# Baro_V3.net
KiCad netlist of a schematic drawn in EAGLE
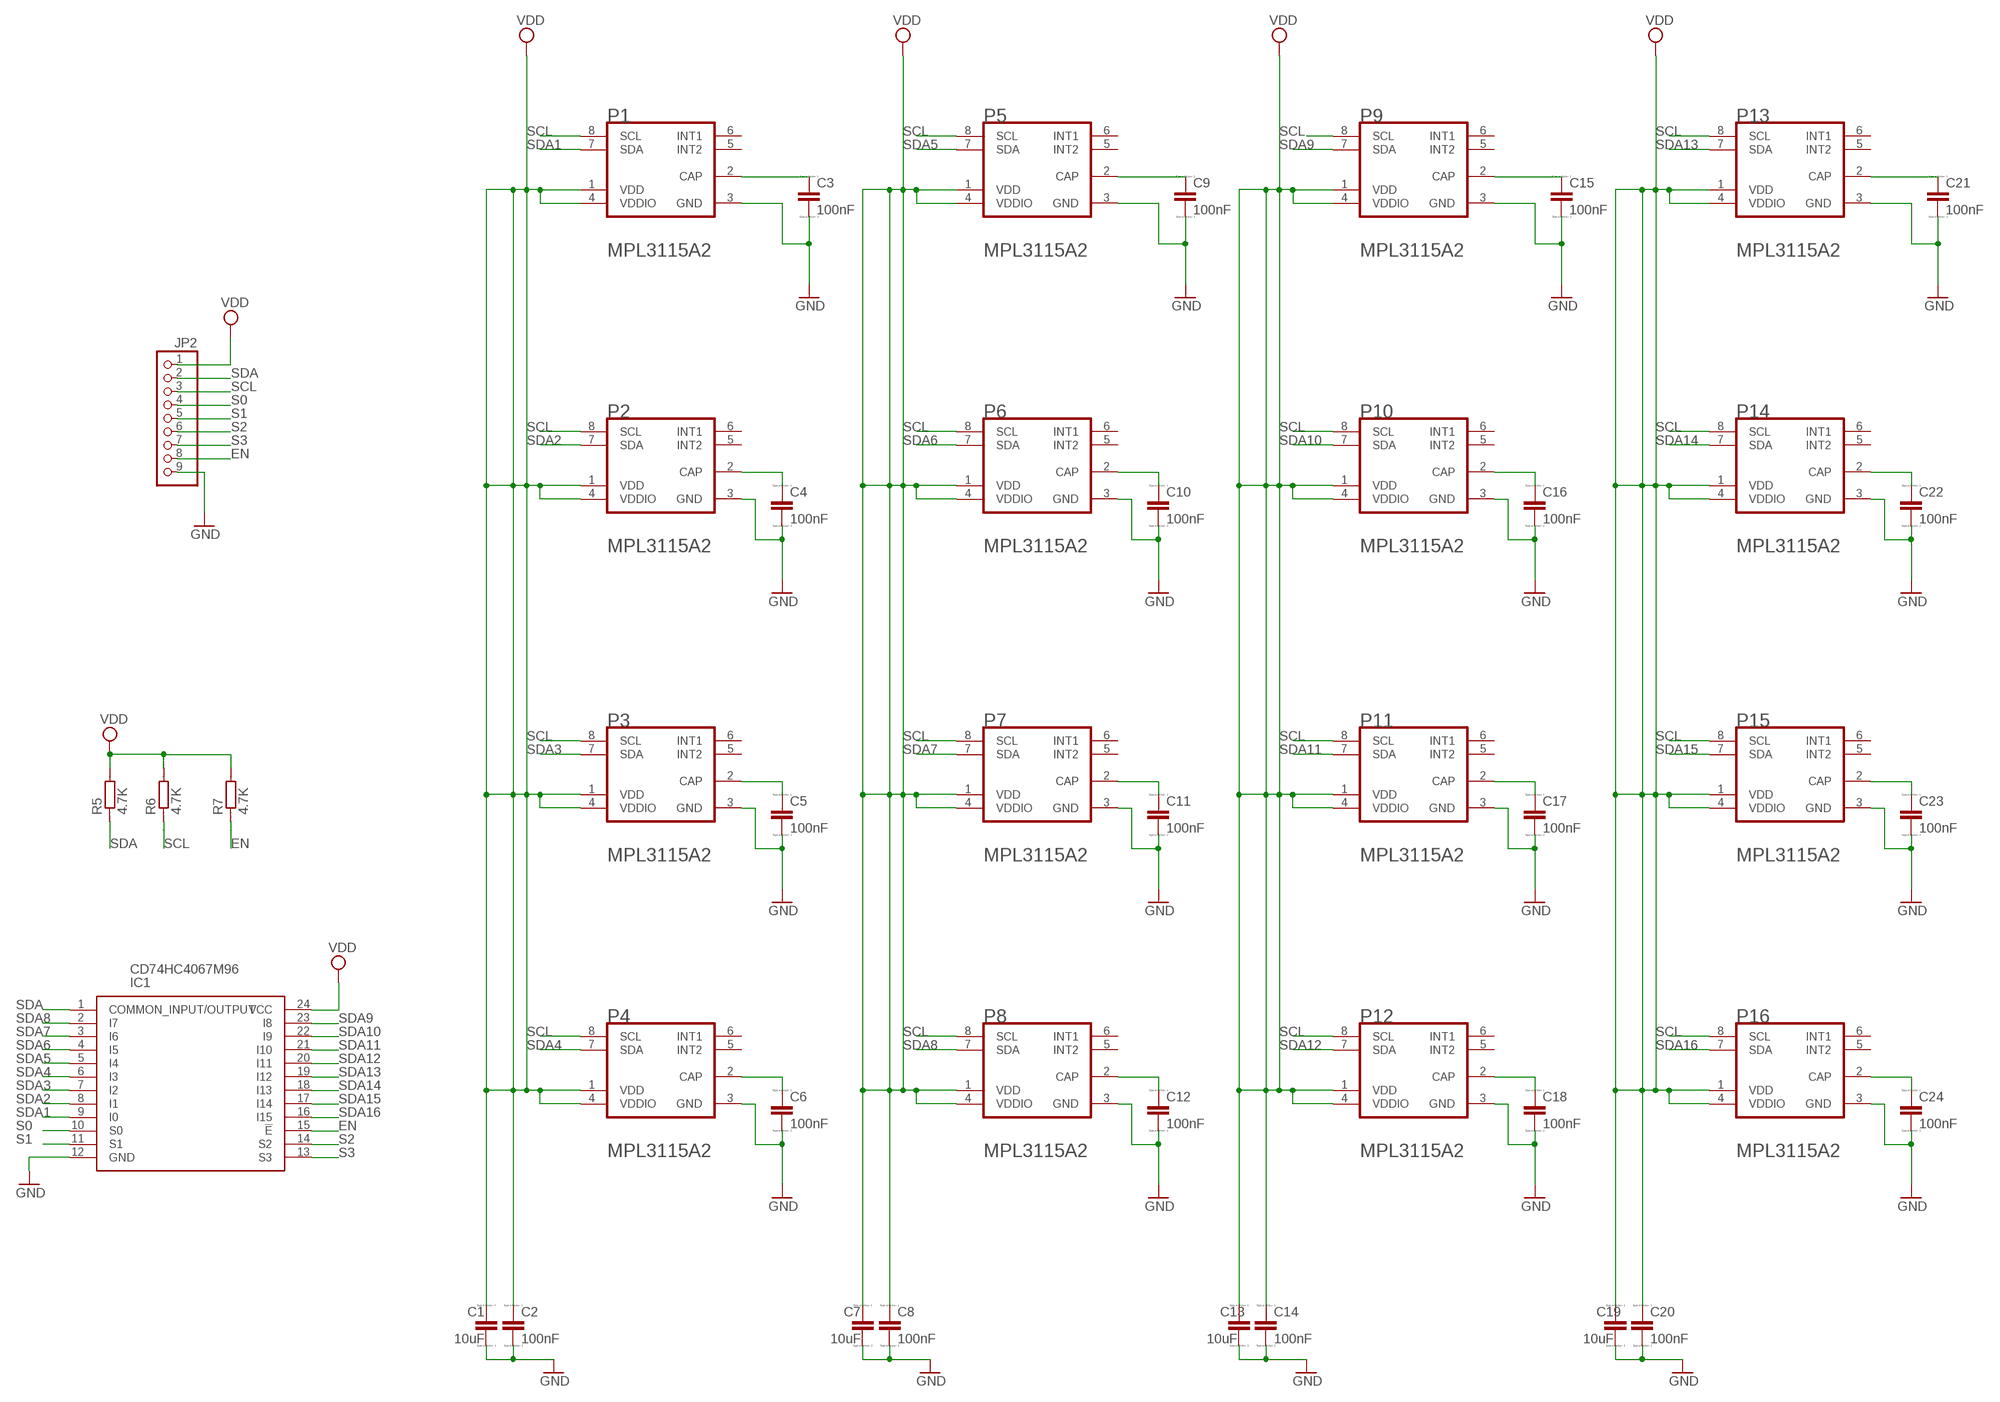
[diagram p0: schematic, sheet 1]

(export (version "E")
  (design (tool "Eeschema 10.0.6"))
  (components
    (comp (ref "C1")
      (value "10uF")
      (footprint "eagle-import:C0603")
      (libsource (lib "eagle-import") (part "CC0603"))
    )
    (comp (ref "C2")
      (value "100nF")
      (footprint "eagle-import:C0805")
      (libsource (lib "eagle-import") (part "C"))
    )
    (comp (ref "C3")
      (value "100nF")
      (footprint "eagle-import:C0805")
      (libsource (lib "eagle-import") (part "C"))
    )
    (comp (ref "C4")
      (value "100nF")
      (footprint "eagle-import:C0805")
      (libsource (lib "eagle-import") (part "C"))
    )
    (comp (ref "C5")
      (value "100nF")
      (footprint "eagle-import:C0805")
      (libsource (lib "eagle-import") (part "C"))
    )
    (comp (ref "C6")
      (value "100nF")
      (footprint "eagle-import:C0805")
      (libsource (lib "eagle-import") (part "C"))
    )
    (comp (ref "C7")
      (value "10uF")
      (footprint "eagle-import:C0603")
      (libsource (lib "eagle-import") (part "CC0603"))
    )
    (comp (ref "C8")
      (value "100nF")
      (footprint "eagle-import:C0805")
      (libsource (lib "eagle-import") (part "C"))
    )
    (comp (ref "C9")
      (value "100nF")
      (footprint "eagle-import:C0805")
      (libsource (lib "eagle-import") (part "C"))
    )
    (comp (ref "C10")
      (value "100nF")
      (footprint "eagle-import:C0805")
      (libsource (lib "eagle-import") (part "C"))
    )
    (comp (ref "C11")
      (value "100nF")
      (footprint "eagle-import:C0805")
      (libsource (lib "eagle-import") (part "C"))
    )
    (comp (ref "C12")
      (value "100nF")
      (footprint "eagle-import:C0805")
      (libsource (lib "eagle-import") (part "C"))
    )
    (comp (ref "C13")
      (value "10uF")
      (footprint "eagle-import:C0603")
      (libsource (lib "eagle-import") (part "CC0603"))
    )
    (comp (ref "C14")
      (value "100nF")
      (footprint "eagle-import:C0805")
      (libsource (lib "eagle-import") (part "C"))
    )
    (comp (ref "C15")
      (value "100nF")
      (footprint "eagle-import:C0805")
      (libsource (lib "eagle-import") (part "C"))
    )
    (comp (ref "C16")
      (value "100nF")
      (footprint "eagle-import:C0805")
      (libsource (lib "eagle-import") (part "C"))
    )
    (comp (ref "C17")
      (value "100nF")
      (footprint "eagle-import:C0805")
      (libsource (lib "eagle-import") (part "C"))
    )
    (comp (ref "C18")
      (value "100nF")
      (footprint "eagle-import:C0805")
      (libsource (lib "eagle-import") (part "C"))
    )
    (comp (ref "C19")
      (value "10uF")
      (footprint "eagle-import:C0603")
      (libsource (lib "eagle-import") (part "CC0603"))
    )
    (comp (ref "C20")
      (value "100nF")
      (footprint "eagle-import:C0805")
      (libsource (lib "eagle-import") (part "C"))
    )
    (comp (ref "C21")
      (value "100nF")
      (footprint "eagle-import:C0805")
      (libsource (lib "eagle-import") (part "C"))
    )
    (comp (ref "C22")
      (value "100nF")
      (footprint "eagle-import:C0805")
      (libsource (lib "eagle-import") (part "C"))
    )
    (comp (ref "C23")
      (value "100nF")
      (footprint "eagle-import:C0805")
      (libsource (lib "eagle-import") (part "C"))
    )
    (comp (ref "C24")
      (value "100nF")
      (footprint "eagle-import:C0805")
      (libsource (lib "eagle-import") (part "C"))
    )
    (comp (ref "IC1")
      (value "CD74HC4067M96")
      (footprint "eagle-import:SOIC127P1030X265-24N")
      (fields (field (name "MOUSER_PART_NUMBER") "595-CD74HC4067M96"))
      (libsource (lib "eagle-import") (part "CD74HC4067M96"))
    )
    (comp (ref "JP2")
      (value "PINHD-1X9")
      (footprint "eagle-import:1X09")
      (libsource (lib "eagle-import") (part "PINHD-1X9"))
    )
    (comp (ref "P1")
      (value "FREESCALE_SEMICONDUCTOR_MPL3115A2FREESCALE_SEMICONDUCTOR_MPL3115A2_0_0")
      (footprint "eagle-import:FREESCALE_SEMICONDUCTOR_MPL3115A2_0")
      (fields (field (name "MF") "Freescale Semiconductor") (field (name "MPN") "MPL3115A2"))
      (libsource (lib "eagle-import") (part "FREESCALE_SEMICONDUCTOR_MPL3115A2FREESCALE_SEMICONDUCTOR_MPL3115A2_0_0"))
    )
    (comp (ref "P2")
      (value "FREESCALE_SEMICONDUCTOR_MPL3115A2FREESCALE_SEMICONDUCTOR_MPL3115A2_0_0")
      (footprint "eagle-import:FREESCALE_SEMICONDUCTOR_MPL3115A2_0")
      (fields (field (name "MF") "Freescale Semiconductor") (field (name "MPN") "MPL3115A2"))
      (libsource (lib "eagle-import") (part "FREESCALE_SEMICONDUCTOR_MPL3115A2FREESCALE_SEMICONDUCTOR_MPL3115A2_0_0"))
    )
    (comp (ref "P3")
      (value "FREESCALE_SEMICONDUCTOR_MPL3115A2FREESCALE_SEMICONDUCTOR_MPL3115A2_0_0")
      (footprint "eagle-import:FREESCALE_SEMICONDUCTOR_MPL3115A2_0")
      (fields (field (name "MF") "Freescale Semiconductor") (field (name "MPN") "MPL3115A2"))
      (libsource (lib "eagle-import") (part "FREESCALE_SEMICONDUCTOR_MPL3115A2FREESCALE_SEMICONDUCTOR_MPL3115A2_0_0"))
    )
    (comp (ref "P4")
      (value "FREESCALE_SEMICONDUCTOR_MPL3115A2FREESCALE_SEMICONDUCTOR_MPL3115A2_0_0")
      (footprint "eagle-import:FREESCALE_SEMICONDUCTOR_MPL3115A2_0")
      (fields (field (name "MF") "Freescale Semiconductor") (field (name "MPN") "MPL3115A2"))
      (libsource (lib "eagle-import") (part "FREESCALE_SEMICONDUCTOR_MPL3115A2FREESCALE_SEMICONDUCTOR_MPL3115A2_0_0"))
    )
    (comp (ref "P5")
      (value "FREESCALE_SEMICONDUCTOR_MPL3115A2FREESCALE_SEMICONDUCTOR_MPL3115A2_0_0")
      (footprint "eagle-import:FREESCALE_SEMICONDUCTOR_MPL3115A2_0")
      (fields (field (name "MF") "Freescale Semiconductor") (field (name "MPN") "MPL3115A2"))
      (libsource (lib "eagle-import") (part "FREESCALE_SEMICONDUCTOR_MPL3115A2FREESCALE_SEMICONDUCTOR_MPL3115A2_0_0"))
    )
    (comp (ref "P6")
      (value "FREESCALE_SEMICONDUCTOR_MPL3115A2FREESCALE_SEMICONDUCTOR_MPL3115A2_0_0")
      (footprint "eagle-import:FREESCALE_SEMICONDUCTOR_MPL3115A2_0")
      (fields (field (name "MF") "Freescale Semiconductor") (field (name "MPN") "MPL3115A2"))
      (libsource (lib "eagle-import") (part "FREESCALE_SEMICONDUCTOR_MPL3115A2FREESCALE_SEMICONDUCTOR_MPL3115A2_0_0"))
    )
    (comp (ref "P7")
      (value "FREESCALE_SEMICONDUCTOR_MPL3115A2FREESCALE_SEMICONDUCTOR_MPL3115A2_0_0")
      (footprint "eagle-import:FREESCALE_SEMICONDUCTOR_MPL3115A2_0")
      (fields (field (name "MF") "Freescale Semiconductor") (field (name "MPN") "MPL3115A2"))
      (libsource (lib "eagle-import") (part "FREESCALE_SEMICONDUCTOR_MPL3115A2FREESCALE_SEMICONDUCTOR_MPL3115A2_0_0"))
    )
    (comp (ref "P8")
      (value "FREESCALE_SEMICONDUCTOR_MPL3115A2FREESCALE_SEMICONDUCTOR_MPL3115A2_0_0")
      (footprint "eagle-import:FREESCALE_SEMICONDUCTOR_MPL3115A2_0")
      (fields (field (name "MF") "Freescale Semiconductor") (field (name "MPN") "MPL3115A2"))
      (libsource (lib "eagle-import") (part "FREESCALE_SEMICONDUCTOR_MPL3115A2FREESCALE_SEMICONDUCTOR_MPL3115A2_0_0"))
    )
    (comp (ref "P9")
      (value "FREESCALE_SEMICONDUCTOR_MPL3115A2FREESCALE_SEMICONDUCTOR_MPL3115A2_0_0")
      (footprint "eagle-import:FREESCALE_SEMICONDUCTOR_MPL3115A2_0")
      (fields (field (name "MF") "Freescale Semiconductor") (field (name "MPN") "MPL3115A2"))
      (libsource (lib "eagle-import") (part "FREESCALE_SEMICONDUCTOR_MPL3115A2FREESCALE_SEMICONDUCTOR_MPL3115A2_0_0"))
    )
    (comp (ref "P10")
      (value "FREESCALE_SEMICONDUCTOR_MPL3115A2FREESCALE_SEMICONDUCTOR_MPL3115A2_0_0")
      (footprint "eagle-import:FREESCALE_SEMICONDUCTOR_MPL3115A2_0")
      (fields (field (name "MF") "Freescale Semiconductor") (field (name "MPN") "MPL3115A2"))
      (libsource (lib "eagle-import") (part "FREESCALE_SEMICONDUCTOR_MPL3115A2FREESCALE_SEMICONDUCTOR_MPL3115A2_0_0"))
    )
    (comp (ref "P11")
      (value "FREESCALE_SEMICONDUCTOR_MPL3115A2FREESCALE_SEMICONDUCTOR_MPL3115A2_0_0")
      (footprint "eagle-import:FREESCALE_SEMICONDUCTOR_MPL3115A2_0")
      (fields (field (name "MF") "Freescale Semiconductor") (field (name "MPN") "MPL3115A2"))
      (libsource (lib "eagle-import") (part "FREESCALE_SEMICONDUCTOR_MPL3115A2FREESCALE_SEMICONDUCTOR_MPL3115A2_0_0"))
    )
    (comp (ref "P12")
      (value "FREESCALE_SEMICONDUCTOR_MPL3115A2FREESCALE_SEMICONDUCTOR_MPL3115A2_0_0")
      (footprint "eagle-import:FREESCALE_SEMICONDUCTOR_MPL3115A2_0")
      (fields (field (name "MF") "Freescale Semiconductor") (field (name "MPN") "MPL3115A2"))
      (libsource (lib "eagle-import") (part "FREESCALE_SEMICONDUCTOR_MPL3115A2FREESCALE_SEMICONDUCTOR_MPL3115A2_0_0"))
    )
    (comp (ref "P13")
      (value "FREESCALE_SEMICONDUCTOR_MPL3115A2FREESCALE_SEMICONDUCTOR_MPL3115A2_0_0")
      (footprint "eagle-import:FREESCALE_SEMICONDUCTOR_MPL3115A2_0")
      (fields (field (name "MF") "Freescale Semiconductor") (field (name "MPN") "MPL3115A2"))
      (libsource (lib "eagle-import") (part "FREESCALE_SEMICONDUCTOR_MPL3115A2FREESCALE_SEMICONDUCTOR_MPL3115A2_0_0"))
    )
    (comp (ref "P14")
      (value "FREESCALE_SEMICONDUCTOR_MPL3115A2FREESCALE_SEMICONDUCTOR_MPL3115A2_0_0")
      (footprint "eagle-import:FREESCALE_SEMICONDUCTOR_MPL3115A2_0")
      (fields (field (name "MF") "Freescale Semiconductor") (field (name "MPN") "MPL3115A2"))
      (libsource (lib "eagle-import") (part "FREESCALE_SEMICONDUCTOR_MPL3115A2FREESCALE_SEMICONDUCTOR_MPL3115A2_0_0"))
    )
    (comp (ref "P15")
      (value "FREESCALE_SEMICONDUCTOR_MPL3115A2FREESCALE_SEMICONDUCTOR_MPL3115A2_0_0")
      (footprint "eagle-import:FREESCALE_SEMICONDUCTOR_MPL3115A2_0")
      (fields (field (name "MF") "Freescale Semiconductor") (field (name "MPN") "MPL3115A2"))
      (libsource (lib "eagle-import") (part "FREESCALE_SEMICONDUCTOR_MPL3115A2FREESCALE_SEMICONDUCTOR_MPL3115A2_0_0"))
    )
    (comp (ref "P16")
      (value "FREESCALE_SEMICONDUCTOR_MPL3115A2FREESCALE_SEMICONDUCTOR_MPL3115A2_0_0")
      (footprint "eagle-import:FREESCALE_SEMICONDUCTOR_MPL3115A2_0")
      (fields (field (name "MF") "Freescale Semiconductor") (field (name "MPN") "MPL3115A2"))
      (libsource (lib "eagle-import") (part "FREESCALE_SEMICONDUCTOR_MPL3115A2FREESCALE_SEMICONDUCTOR_MPL3115A2_0_0"))
    )
    (comp (ref "R5")
      (value "4.7K")
      (footprint "eagle-import:R0603")
      (libsource (lib "eagle-import") (part "RR0603"))
    )
    (comp (ref "R6")
      (value "4.7K")
      (footprint "eagle-import:R0603")
      (libsource (lib "eagle-import") (part "RR0603"))
    )
    (comp (ref "R7")
      (value "4.7K")
      (footprint "eagle-import:R0603")
      (libsource (lib "eagle-import") (part "RR0603"))
    )
  )
  (nets
    (net (code "1") (name "/EN") (class "Default")
      (node (ref "IC1") (pin "15") (pinfunction "~{E}_15") (pintype "bidirectional"))
      (node (ref "JP2") (pin "8") (pinfunction "8_8") (pintype "passive"))
      (node (ref "R7") (pin "1") (pinfunction "1_1") (pintype "passive"))
    )
    (net (code "2") (name "/S0") (class "Default")
      (node (ref "IC1") (pin "10") (pinfunction "S0_10") (pintype "bidirectional"))
      (node (ref "JP2") (pin "4") (pinfunction "4_4") (pintype "passive"))
    )
    (net (code "3") (name "/S1") (class "Default")
      (node (ref "IC1") (pin "11") (pinfunction "S1_11") (pintype "bidirectional"))
      (node (ref "JP2") (pin "5") (pinfunction "5_5") (pintype "passive"))
    )
    (net (code "4") (name "/S2") (class "Default")
      (node (ref "IC1") (pin "14") (pinfunction "S2_14") (pintype "bidirectional"))
      (node (ref "JP2") (pin "6") (pinfunction "6_6") (pintype "passive"))
    )
    (net (code "5") (name "/S3") (class "Default")
      (node (ref "IC1") (pin "13") (pinfunction "S3_13") (pintype "bidirectional"))
      (node (ref "JP2") (pin "7") (pinfunction "7_7") (pintype "passive"))
    )
    (net (code "6") (name "/SCL") (class "Default")
      (node (ref "JP2") (pin "3") (pinfunction "3_3") (pintype "passive"))
      (node (ref "P1") (pin "8") (pinfunction "SCL_8") (pintype "input"))
      (node (ref "P10") (pin "8") (pinfunction "SCL_8") (pintype "input"))
      (node (ref "P11") (pin "8") (pinfunction "SCL_8") (pintype "input"))
      (node (ref "P12") (pin "8") (pinfunction "SCL_8") (pintype "input"))
      (node (ref "P13") (pin "8") (pinfunction "SCL_8") (pintype "input"))
      (node (ref "P14") (pin "8") (pinfunction "SCL_8") (pintype "input"))
      (node (ref "P15") (pin "8") (pinfunction "SCL_8") (pintype "input"))
      (node (ref "P16") (pin "8") (pinfunction "SCL_8") (pintype "input"))
      (node (ref "P2") (pin "8") (pinfunction "SCL_8") (pintype "input"))
      (node (ref "P3") (pin "8") (pinfunction "SCL_8") (pintype "input"))
      (node (ref "P4") (pin "8") (pinfunction "SCL_8") (pintype "input"))
      (node (ref "P5") (pin "8") (pinfunction "SCL_8") (pintype "input"))
      (node (ref "P6") (pin "8") (pinfunction "SCL_8") (pintype "input"))
      (node (ref "P7") (pin "8") (pinfunction "SCL_8") (pintype "input"))
      (node (ref "P8") (pin "8") (pinfunction "SCL_8") (pintype "input"))
      (node (ref "P9") (pin "8") (pinfunction "SCL_8") (pintype "input"))
      (node (ref "R6") (pin "1") (pinfunction "1_1") (pintype "passive"))
    )
    (net (code "7") (name "/SDA") (class "Default")
      (node (ref "IC1") (pin "1") (pinfunction "COMMON_INPUT/OUTPUT_1") (pintype "bidirectional"))
      (node (ref "JP2") (pin "2") (pinfunction "2_2") (pintype "passive"))
      (node (ref "R5") (pin "1") (pinfunction "1_1") (pintype "passive"))
    )
    (net (code "8") (name "/SDA1") (class "Default")
      (node (ref "IC1") (pin "9") (pinfunction "I0_9") (pintype "bidirectional"))
      (node (ref "P1") (pin "7") (pinfunction "SDA_7") (pintype "bidirectional"))
    )
    (net (code "9") (name "/SDA2") (class "Default")
      (node (ref "IC1") (pin "8") (pinfunction "I1_8") (pintype "bidirectional"))
      (node (ref "P2") (pin "7") (pinfunction "SDA_7") (pintype "bidirectional"))
    )
    (net (code "10") (name "/SDA3") (class "Default")
      (node (ref "IC1") (pin "7") (pinfunction "I2_7") (pintype "bidirectional"))
      (node (ref "P3") (pin "7") (pinfunction "SDA_7") (pintype "bidirectional"))
    )
    (net (code "11") (name "/SDA4") (class "Default")
      (node (ref "IC1") (pin "6") (pinfunction "I3_6") (pintype "bidirectional"))
      (node (ref "P4") (pin "7") (pinfunction "SDA_7") (pintype "bidirectional"))
    )
    (net (code "12") (name "/SDA5") (class "Default")
      (node (ref "IC1") (pin "5") (pinfunction "I4_5") (pintype "bidirectional"))
      (node (ref "P5") (pin "7") (pinfunction "SDA_7") (pintype "bidirectional"))
    )
    (net (code "13") (name "/SDA6") (class "Default")
      (node (ref "IC1") (pin "4") (pinfunction "I5_4") (pintype "bidirectional"))
      (node (ref "P6") (pin "7") (pinfunction "SDA_7") (pintype "bidirectional"))
    )
    (net (code "14") (name "/SDA7") (class "Default")
      (node (ref "IC1") (pin "3") (pinfunction "I6_3") (pintype "bidirectional"))
      (node (ref "P7") (pin "7") (pinfunction "SDA_7") (pintype "bidirectional"))
    )
    (net (code "15") (name "/SDA8") (class "Default")
      (node (ref "IC1") (pin "2") (pinfunction "I7_2") (pintype "bidirectional"))
      (node (ref "P8") (pin "7") (pinfunction "SDA_7") (pintype "bidirectional"))
    )
    (net (code "16") (name "/SDA9") (class "Default")
      (node (ref "IC1") (pin "23") (pinfunction "I8_23") (pintype "bidirectional"))
      (node (ref "P9") (pin "7") (pinfunction "SDA_7") (pintype "bidirectional"))
    )
    (net (code "17") (name "/SDA10") (class "Default")
      (node (ref "IC1") (pin "22") (pinfunction "I9_22") (pintype "bidirectional"))
      (node (ref "P10") (pin "7") (pinfunction "SDA_7") (pintype "bidirectional"))
    )
    (net (code "18") (name "/SDA11") (class "Default")
      (node (ref "IC1") (pin "21") (pinfunction "I10_21") (pintype "bidirectional"))
      (node (ref "P11") (pin "7") (pinfunction "SDA_7") (pintype "bidirectional"))
    )
    (net (code "19") (name "/SDA12") (class "Default")
      (node (ref "IC1") (pin "20") (pinfunction "I11_20") (pintype "bidirectional"))
      (node (ref "P12") (pin "7") (pinfunction "SDA_7") (pintype "bidirectional"))
    )
    (net (code "20") (name "/SDA13") (class "Default")
      (node (ref "IC1") (pin "19") (pinfunction "I12_19") (pintype "bidirectional"))
      (node (ref "P13") (pin "7") (pinfunction "SDA_7") (pintype "bidirectional"))
    )
    (net (code "21") (name "/SDA14") (class "Default")
      (node (ref "IC1") (pin "18") (pinfunction "I13_18") (pintype "bidirectional"))
      (node (ref "P14") (pin "7") (pinfunction "SDA_7") (pintype "bidirectional"))
    )
    (net (code "22") (name "/SDA15") (class "Default")
      (node (ref "IC1") (pin "17") (pinfunction "I14_17") (pintype "bidirectional"))
      (node (ref "P15") (pin "7") (pinfunction "SDA_7") (pintype "bidirectional"))
    )
    (net (code "23") (name "/SDA16") (class "Default")
      (node (ref "IC1") (pin "16") (pinfunction "I15_16") (pintype "bidirectional"))
      (node (ref "P16") (pin "7") (pinfunction "SDA_7") (pintype "bidirectional"))
    )
    (net (code "24") (name "GND") (class "Default")
      (node (ref "C1") (pin "2") (pinfunction "2_2") (pintype "passive"))
      (node (ref "C10") (pin "2") (pinfunction "2_2") (pintype "passive"))
      (node (ref "C11") (pin "2") (pinfunction "2_2") (pintype "passive"))
      (node (ref "C12") (pin "2") (pinfunction "2_2") (pintype "passive"))
      (node (ref "C13") (pin "2") (pinfunction "2_2") (pintype "passive"))
      (node (ref "C14") (pin "2") (pinfunction "2_2") (pintype "passive"))
      (node (ref "C15") (pin "2") (pinfunction "2_2") (pintype "passive"))
      (node (ref "C16") (pin "2") (pinfunction "2_2") (pintype "passive"))
      (node (ref "C17") (pin "2") (pinfunction "2_2") (pintype "passive"))
      (node (ref "C18") (pin "2") (pinfunction "2_2") (pintype "passive"))
      (node (ref "C19") (pin "2") (pinfunction "2_2") (pintype "passive"))
      (node (ref "C2") (pin "2") (pinfunction "2_2") (pintype "passive"))
      (node (ref "C20") (pin "2") (pinfunction "2_2") (pintype "passive"))
      (node (ref "C21") (pin "2") (pinfunction "2_2") (pintype "passive"))
      (node (ref "C22") (pin "2") (pinfunction "2_2") (pintype "passive"))
      (node (ref "C23") (pin "2") (pinfunction "2_2") (pintype "passive"))
      (node (ref "C24") (pin "2") (pinfunction "2_2") (pintype "passive"))
      (node (ref "C3") (pin "2") (pinfunction "2_2") (pintype "passive"))
      (node (ref "C4") (pin "2") (pinfunction "2_2") (pintype "passive"))
      (node (ref "C5") (pin "2") (pinfunction "2_2") (pintype "passive"))
      (node (ref "C6") (pin "2") (pinfunction "2_2") (pintype "passive"))
      (node (ref "C7") (pin "2") (pinfunction "2_2") (pintype "passive"))
      (node (ref "C8") (pin "2") (pinfunction "2_2") (pintype "passive"))
      (node (ref "C9") (pin "2") (pinfunction "2_2") (pintype "passive"))
      (node (ref "IC1") (pin "12") (pinfunction "GND_12") (pintype "bidirectional"))
      (node (ref "JP2") (pin "9") (pinfunction "9_9") (pintype "passive"))
      (node (ref "P1") (pin "3") (pinfunction "GND_3") (pintype "power_in"))
      (node (ref "P10") (pin "3") (pinfunction "GND_3") (pintype "power_in"))
      (node (ref "P11") (pin "3") (pinfunction "GND_3") (pintype "power_in"))
      (node (ref "P12") (pin "3") (pinfunction "GND_3") (pintype "power_in"))
      (node (ref "P13") (pin "3") (pinfunction "GND_3") (pintype "power_in"))
      (node (ref "P14") (pin "3") (pinfunction "GND_3") (pintype "power_in"))
      (node (ref "P15") (pin "3") (pinfunction "GND_3") (pintype "power_in"))
      (node (ref "P16") (pin "3") (pinfunction "GND_3") (pintype "power_in"))
      (node (ref "P2") (pin "3") (pinfunction "GND_3") (pintype "power_in"))
      (node (ref "P3") (pin "3") (pinfunction "GND_3") (pintype "power_in"))
      (node (ref "P4") (pin "3") (pinfunction "GND_3") (pintype "power_in"))
      (node (ref "P5") (pin "3") (pinfunction "GND_3") (pintype "power_in"))
      (node (ref "P6") (pin "3") (pinfunction "GND_3") (pintype "power_in"))
      (node (ref "P7") (pin "3") (pinfunction "GND_3") (pintype "power_in"))
      (node (ref "P8") (pin "3") (pinfunction "GND_3") (pintype "power_in"))
      (node (ref "P9") (pin "3") (pinfunction "GND_3") (pintype "power_in"))
    )
    (net (code "25") (name "Net-(P1-CAP)") (class "Default")
      (node (ref "C3") (pin "1") (pinfunction "1_1") (pintype "passive"))
      (node (ref "P1") (pin "2") (pinfunction "CAP_2") (pintype "passive"))
    )
    (net (code "26") (name "Net-(P2-CAP)") (class "Default")
      (node (ref "C4") (pin "1") (pinfunction "1_1") (pintype "passive"))
      (node (ref "P2") (pin "2") (pinfunction "CAP_2") (pintype "passive"))
    )
    (net (code "27") (name "Net-(P3-CAP)") (class "Default")
      (node (ref "C5") (pin "1") (pinfunction "1_1") (pintype "passive"))
      (node (ref "P3") (pin "2") (pinfunction "CAP_2") (pintype "passive"))
    )
    (net (code "28") (name "Net-(P4-CAP)") (class "Default")
      (node (ref "C6") (pin "1") (pinfunction "1_1") (pintype "passive"))
      (node (ref "P4") (pin "2") (pinfunction "CAP_2") (pintype "passive"))
    )
    (net (code "29") (name "Net-(P5-CAP)") (class "Default")
      (node (ref "C9") (pin "1") (pinfunction "1_1") (pintype "passive"))
      (node (ref "P5") (pin "2") (pinfunction "CAP_2") (pintype "passive"))
    )
    (net (code "30") (name "Net-(P6-CAP)") (class "Default")
      (node (ref "C10") (pin "1") (pinfunction "1_1") (pintype "passive"))
      (node (ref "P6") (pin "2") (pinfunction "CAP_2") (pintype "passive"))
    )
    (net (code "31") (name "Net-(P7-CAP)") (class "Default")
      (node (ref "C11") (pin "1") (pinfunction "1_1") (pintype "passive"))
      (node (ref "P7") (pin "2") (pinfunction "CAP_2") (pintype "passive"))
    )
    (net (code "32") (name "Net-(P8-CAP)") (class "Default")
      (node (ref "C12") (pin "1") (pinfunction "1_1") (pintype "passive"))
      (node (ref "P8") (pin "2") (pinfunction "CAP_2") (pintype "passive"))
    )
    (net (code "33") (name "Net-(P9-CAP)") (class "Default")
      (node (ref "C15") (pin "1") (pinfunction "1_1") (pintype "passive"))
      (node (ref "P9") (pin "2") (pinfunction "CAP_2") (pintype "passive"))
    )
    (net (code "34") (name "Net-(P10-CAP)") (class "Default")
      (node (ref "C16") (pin "1") (pinfunction "1_1") (pintype "passive"))
      (node (ref "P10") (pin "2") (pinfunction "CAP_2") (pintype "passive"))
    )
    (net (code "35") (name "Net-(P11-CAP)") (class "Default")
      (node (ref "C17") (pin "1") (pinfunction "1_1") (pintype "passive"))
      (node (ref "P11") (pin "2") (pinfunction "CAP_2") (pintype "passive"))
    )
    (net (code "36") (name "Net-(P12-CAP)") (class "Default")
      (node (ref "C18") (pin "1") (pinfunction "1_1") (pintype "passive"))
      (node (ref "P12") (pin "2") (pinfunction "CAP_2") (pintype "passive"))
    )
    (net (code "37") (name "Net-(P13-CAP)") (class "Default")
      (node (ref "C21") (pin "1") (pinfunction "1_1") (pintype "passive"))
      (node (ref "P13") (pin "2") (pinfunction "CAP_2") (pintype "passive"))
    )
    (net (code "38") (name "Net-(P14-CAP)") (class "Default")
      (node (ref "C22") (pin "1") (pinfunction "1_1") (pintype "passive"))
      (node (ref "P14") (pin "2") (pinfunction "CAP_2") (pintype "passive"))
    )
    (net (code "39") (name "Net-(P15-CAP)") (class "Default")
      (node (ref "C23") (pin "1") (pinfunction "1_1") (pintype "passive"))
      (node (ref "P15") (pin "2") (pinfunction "CAP_2") (pintype "passive"))
    )
    (net (code "40") (name "Net-(P16-CAP)") (class "Default")
      (node (ref "C24") (pin "1") (pinfunction "1_1") (pintype "passive"))
      (node (ref "P16") (pin "2") (pinfunction "CAP_2") (pintype "passive"))
    )
    (net (code "41") (name "VDD") (class "Default")
      (node (ref "C1") (pin "1") (pinfunction "1_1") (pintype "passive"))
      (node (ref "C13") (pin "1") (pinfunction "1_1") (pintype "passive"))
      (node (ref "C14") (pin "1") (pinfunction "1_1") (pintype "passive"))
      (node (ref "C19") (pin "1") (pinfunction "1_1") (pintype "passive"))
      (node (ref "C2") (pin "1") (pinfunction "1_1") (pintype "passive"))
      (node (ref "C20") (pin "1") (pinfunction "1_1") (pintype "passive"))
      (node (ref "C7") (pin "1") (pinfunction "1_1") (pintype "passive"))
      (node (ref "C8") (pin "1") (pinfunction "1_1") (pintype "passive"))
      (node (ref "IC1") (pin "24") (pinfunction "VCC_24") (pintype "bidirectional"))
      (node (ref "JP2") (pin "1") (pinfunction "1_1") (pintype "passive"))
      (node (ref "P1") (pin "1") (pinfunction "VDD_1") (pintype "power_in"))
      (node (ref "P1") (pin "4") (pinfunction "VDDIO_4") (pintype "power_in"))
      (node (ref "P10") (pin "1") (pinfunction "VDD_1") (pintype "power_in"))
      (node (ref "P10") (pin "4") (pinfunction "VDDIO_4") (pintype "power_in"))
      (node (ref "P11") (pin "1") (pinfunction "VDD_1") (pintype "power_in"))
      (node (ref "P11") (pin "4") (pinfunction "VDDIO_4") (pintype "power_in"))
      (node (ref "P12") (pin "1") (pinfunction "VDD_1") (pintype "power_in"))
      (node (ref "P12") (pin "4") (pinfunction "VDDIO_4") (pintype "power_in"))
      (node (ref "P13") (pin "1") (pinfunction "VDD_1") (pintype "power_in"))
      (node (ref "P13") (pin "4") (pinfunction "VDDIO_4") (pintype "power_in"))
      (node (ref "P14") (pin "1") (pinfunction "VDD_1") (pintype "power_in"))
      (node (ref "P14") (pin "4") (pinfunction "VDDIO_4") (pintype "power_in"))
      (node (ref "P15") (pin "1") (pinfunction "VDD_1") (pintype "power_in"))
      (node (ref "P15") (pin "4") (pinfunction "VDDIO_4") (pintype "power_in"))
      (node (ref "P16") (pin "1") (pinfunction "VDD_1") (pintype "power_in"))
      (node (ref "P16") (pin "4") (pinfunction "VDDIO_4") (pintype "power_in"))
      (node (ref "P2") (pin "1") (pinfunction "VDD_1") (pintype "power_in"))
      (node (ref "P2") (pin "4") (pinfunction "VDDIO_4") (pintype "power_in"))
      (node (ref "P3") (pin "1") (pinfunction "VDD_1") (pintype "power_in"))
      (node (ref "P3") (pin "4") (pinfunction "VDDIO_4") (pintype "power_in"))
      (node (ref "P4") (pin "1") (pinfunction "VDD_1") (pintype "power_in"))
      (node (ref "P4") (pin "4") (pinfunction "VDDIO_4") (pintype "power_in"))
      (node (ref "P5") (pin "1") (pinfunction "VDD_1") (pintype "power_in"))
      (node (ref "P5") (pin "4") (pinfunction "VDDIO_4") (pintype "power_in"))
      (node (ref "P6") (pin "1") (pinfunction "VDD_1") (pintype "power_in"))
      (node (ref "P6") (pin "4") (pinfunction "VDDIO_4") (pintype "power_in"))
      (node (ref "P7") (pin "1") (pinfunction "VDD_1") (pintype "power_in"))
      (node (ref "P7") (pin "4") (pinfunction "VDDIO_4") (pintype "power_in"))
      (node (ref "P8") (pin "1") (pinfunction "VDD_1") (pintype "power_in"))
      (node (ref "P8") (pin "4") (pinfunction "VDDIO_4") (pintype "power_in"))
      (node (ref "P9") (pin "1") (pinfunction "VDD_1") (pintype "power_in"))
      (node (ref "P9") (pin "4") (pinfunction "VDDIO_4") (pintype "power_in"))
      (node (ref "R5") (pin "2") (pinfunction "2_2") (pintype "passive"))
      (node (ref "R6") (pin "2") (pinfunction "2_2") (pintype "passive"))
      (node (ref "R7") (pin "2") (pinfunction "2_2") (pintype "passive"))
    )
    (net (code "42") (name "unconnected-(P1-INT1-Pad6)") (class "Default")
      (node (ref "P1") (pin "6") (pinfunction "INT1_6") (pintype "output"))
    )
    (net (code "43") (name "unconnected-(P1-INT2-Pad5)") (class "Default")
      (node (ref "P1") (pin "5") (pinfunction "INT2_5") (pintype "output"))
    )
    (net (code "44") (name "unconnected-(P2-INT1-Pad6)") (class "Default")
      (node (ref "P2") (pin "6") (pinfunction "INT1_6") (pintype "output"))
    )
    (net (code "45") (name "unconnected-(P2-INT2-Pad5)") (class "Default")
      (node (ref "P2") (pin "5") (pinfunction "INT2_5") (pintype "output"))
    )
    (net (code "46") (name "unconnected-(P3-INT1-Pad6)") (class "Default")
      (node (ref "P3") (pin "6") (pinfunction "INT1_6") (pintype "output"))
    )
    (net (code "47") (name "unconnected-(P3-INT2-Pad5)") (class "Default")
      (node (ref "P3") (pin "5") (pinfunction "INT2_5") (pintype "output"))
    )
    (net (code "48") (name "unconnected-(P4-INT1-Pad6)") (class "Default")
      (node (ref "P4") (pin "6") (pinfunction "INT1_6") (pintype "output"))
    )
    (net (code "49") (name "unconnected-(P4-INT2-Pad5)") (class "Default")
      (node (ref "P4") (pin "5") (pinfunction "INT2_5") (pintype "output"))
    )
    (net (code "50") (name "unconnected-(P5-INT1-Pad6)") (class "Default")
      (node (ref "P5") (pin "6") (pinfunction "INT1_6") (pintype "output"))
    )
    (net (code "51") (name "unconnected-(P5-INT2-Pad5)") (class "Default")
      (node (ref "P5") (pin "5") (pinfunction "INT2_5") (pintype "output"))
    )
    (net (code "52") (name "unconnected-(P6-INT1-Pad6)") (class "Default")
      (node (ref "P6") (pin "6") (pinfunction "INT1_6") (pintype "output"))
    )
    (net (code "53") (name "unconnected-(P6-INT2-Pad5)") (class "Default")
      (node (ref "P6") (pin "5") (pinfunction "INT2_5") (pintype "output"))
    )
    (net (code "54") (name "unconnected-(P7-INT1-Pad6)") (class "Default")
      (node (ref "P7") (pin "6") (pinfunction "INT1_6") (pintype "output"))
    )
    (net (code "55") (name "unconnected-(P7-INT2-Pad5)") (class "Default")
      (node (ref "P7") (pin "5") (pinfunction "INT2_5") (pintype "output"))
    )
    (net (code "56") (name "unconnected-(P8-INT1-Pad6)") (class "Default")
      (node (ref "P8") (pin "6") (pinfunction "INT1_6") (pintype "output"))
    )
    (net (code "57") (name "unconnected-(P8-INT2-Pad5)") (class "Default")
      (node (ref "P8") (pin "5") (pinfunction "INT2_5") (pintype "output"))
    )
    (net (code "58") (name "unconnected-(P9-INT1-Pad6)") (class "Default")
      (node (ref "P9") (pin "6") (pinfunction "INT1_6") (pintype "output"))
    )
    (net (code "59") (name "unconnected-(P9-INT2-Pad5)") (class "Default")
      (node (ref "P9") (pin "5") (pinfunction "INT2_5") (pintype "output"))
    )
    (net (code "60") (name "unconnected-(P10-INT1-Pad6)") (class "Default")
      (node (ref "P10") (pin "6") (pinfunction "INT1_6") (pintype "output"))
    )
    (net (code "61") (name "unconnected-(P10-INT2-Pad5)") (class "Default")
      (node (ref "P10") (pin "5") (pinfunction "INT2_5") (pintype "output"))
    )
    (net (code "62") (name "unconnected-(P11-INT1-Pad6)") (class "Default")
      (node (ref "P11") (pin "6") (pinfunction "INT1_6") (pintype "output"))
    )
    (net (code "63") (name "unconnected-(P11-INT2-Pad5)") (class "Default")
      (node (ref "P11") (pin "5") (pinfunction "INT2_5") (pintype "output"))
    )
    (net (code "64") (name "unconnected-(P12-INT1-Pad6)") (class "Default")
      (node (ref "P12") (pin "6") (pinfunction "INT1_6") (pintype "output"))
    )
    (net (code "65") (name "unconnected-(P12-INT2-Pad5)") (class "Default")
      (node (ref "P12") (pin "5") (pinfunction "INT2_5") (pintype "output"))
    )
    (net (code "66") (name "unconnected-(P13-INT1-Pad6)") (class "Default")
      (node (ref "P13") (pin "6") (pinfunction "INT1_6") (pintype "output"))
    )
    (net (code "67") (name "unconnected-(P13-INT2-Pad5)") (class "Default")
      (node (ref "P13") (pin "5") (pinfunction "INT2_5") (pintype "output"))
    )
    (net (code "68") (name "unconnected-(P14-INT1-Pad6)") (class "Default")
      (node (ref "P14") (pin "6") (pinfunction "INT1_6") (pintype "output"))
    )
    (net (code "69") (name "unconnected-(P14-INT2-Pad5)") (class "Default")
      (node (ref "P14") (pin "5") (pinfunction "INT2_5") (pintype "output"))
    )
    (net (code "70") (name "unconnected-(P15-INT1-Pad6)") (class "Default")
      (node (ref "P15") (pin "6") (pinfunction "INT1_6") (pintype "output"))
    )
    (net (code "71") (name "unconnected-(P15-INT2-Pad5)") (class "Default")
      (node (ref "P15") (pin "5") (pinfunction "INT2_5") (pintype "output"))
    )
    (net (code "72") (name "unconnected-(P16-INT1-Pad6)") (class "Default")
      (node (ref "P16") (pin "6") (pinfunction "INT1_6") (pintype "output"))
    )
    (net (code "73") (name "unconnected-(P16-INT2-Pad5)") (class "Default")
      (node (ref "P16") (pin "5") (pinfunction "INT2_5") (pintype "output"))
    )
  )
)
